# xiao-grove-shield.net
KiCad netlist of a schematic drawn in EAGLE
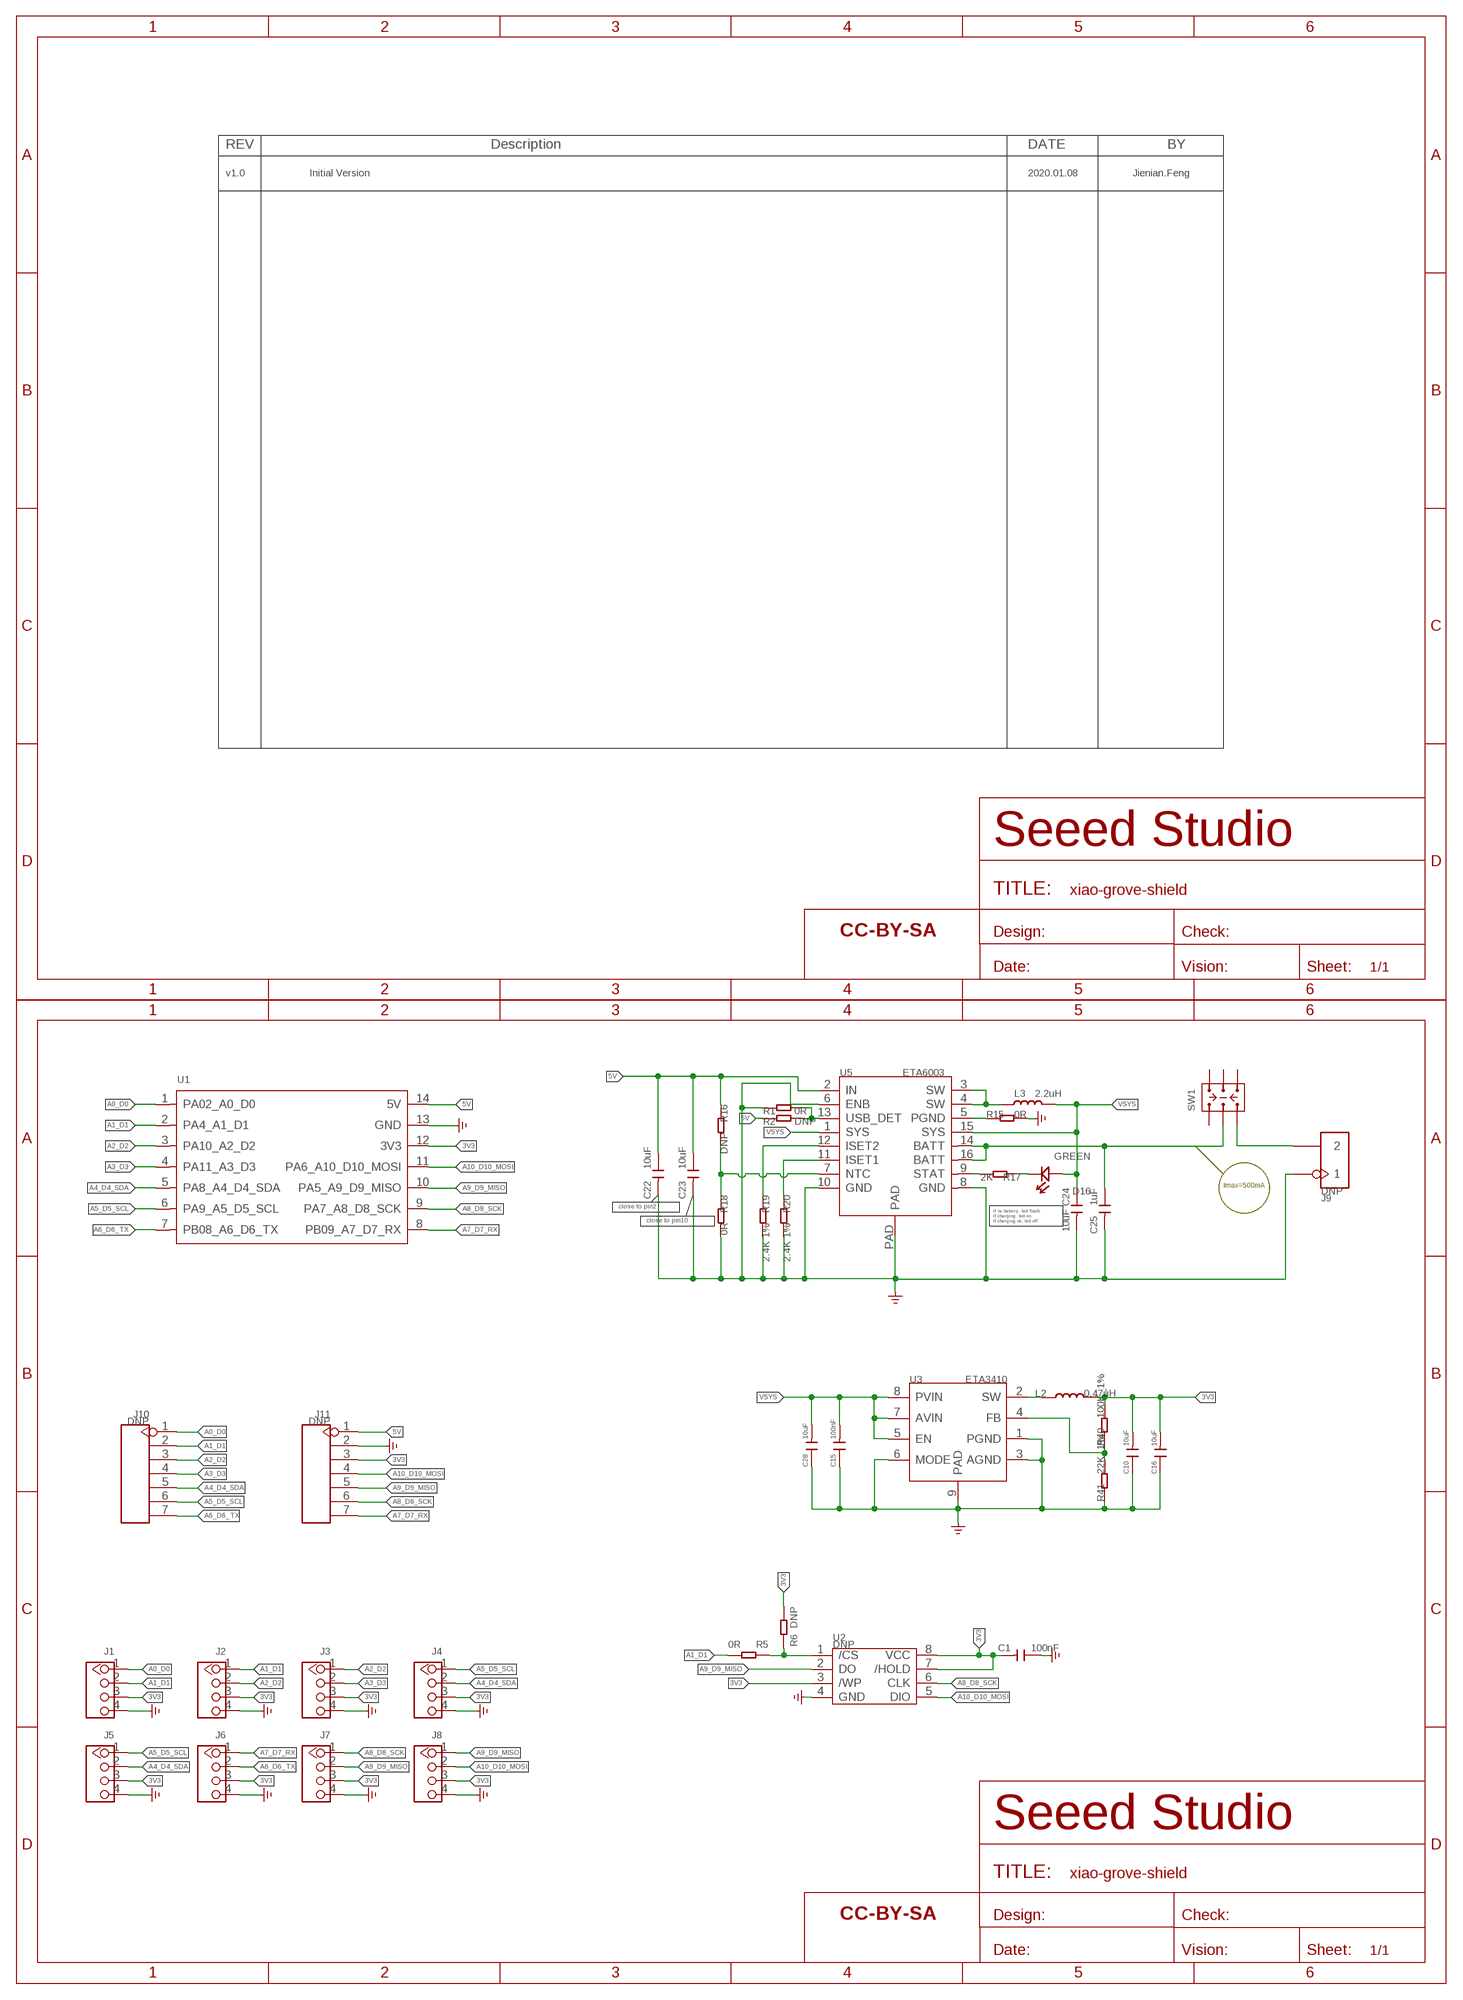
[diagram p0: schematic, sheet 1]

(export (version "E")
  (design (tool "Eeschema 10.0.6"))
  (components
    (comp (ref "C1")
      (value "100nF")
      (footprint "eagle-import:C0402")
      (libsource (lib "eagle-import") (part "CAP-0402"))
    )
    (comp (ref "C10")
      (value "10uF")
      (footprint "eagle-import:C0603")
      (libsource (lib "eagle-import") (part "CAP-0603"))
    )
    (comp (ref "C15")
      (value "100nF")
      (footprint "eagle-import:C0402")
      (libsource (lib "eagle-import") (part "C-0402"))
    )
    (comp (ref "C16")
      (value "10uF")
      (footprint "eagle-import:C0603")
      (libsource (lib "eagle-import") (part "CAP-0603"))
    )
    (comp (ref "C22")
      (value "10uF")
      (footprint "eagle-import:C0603")
      (libsource (lib "eagle-import") (part "CAP-0603"))
    )
    (comp (ref "C23")
      (value "10uF")
      (footprint "eagle-import:C0603")
      (libsource (lib "eagle-import") (part "CAP-0603"))
    )
    (comp (ref "C24")
      (value "10uF")
      (footprint "eagle-import:C0603")
      (libsource (lib "eagle-import") (part "CAP-0603"))
    )
    (comp (ref "C25")
      (value "1uF")
      (footprint "eagle-import:C0402")
      (libsource (lib "eagle-import") (part "C-0402"))
    )
    (comp (ref "C28")
      (value "10uF")
      (footprint "eagle-import:C0603")
      (libsource (lib "eagle-import") (part "CAP-0603"))
    )
    (comp (ref "D16")
      (value "GREEN")
      (footprint "eagle-import:LED-0402")
      (libsource (lib "eagle-import") (part "LED-0402"))
    )
    (comp (ref "FR1")
      (value "SEEEDSTUDIO-OPEN-SCH-FRAME")
      (footprint "eagle-import:SEEEDSTUDIO-PCB-FRAME")
      (libsource (lib "eagle-import") (part "SEEEDSTUDIO-OPEN-SCH-FRAME"))
    )
    (comp (ref "FR2")
      (value "SEEEDSTUDIO-OPEN-SCH-FRAME")
      (footprint "eagle-import:SEEEDSTUDIO-PCB-FRAME")
      (libsource (lib "eagle-import") (part "SEEEDSTUDIO-OPEN-SCH-FRAME"))
    )
    (comp (ref "J1")
      (value "GROVE-CONNECTOR-DIP-320110033")
      (footprint "eagle-import:HW4-2.0")
      (libsource (lib "eagle-import") (part "GROVE-CONNECTOR-DIP-320110033"))
    )
    (comp (ref "J2")
      (value "GROVE-CONNECTOR-DIP-320110033")
      (footprint "eagle-import:HW4-2.0")
      (libsource (lib "eagle-import") (part "GROVE-CONNECTOR-DIP-320110033"))
    )
    (comp (ref "J3")
      (value "GROVE-CONNECTOR-DIP-320110033")
      (footprint "eagle-import:HW4-2.0")
      (libsource (lib "eagle-import") (part "GROVE-CONNECTOR-DIP-320110033"))
    )
    (comp (ref "J4")
      (value "GROVE-CONNECTOR-DIP-320110033")
      (footprint "eagle-import:HW4-2.0")
      (libsource (lib "eagle-import") (part "GROVE-CONNECTOR-DIP-320110033"))
    )
    (comp (ref "J5")
      (value "GROVE-CONNECTOR-DIP-320110033")
      (footprint "eagle-import:HW4-2.0")
      (libsource (lib "eagle-import") (part "GROVE-CONNECTOR-DIP-320110033"))
    )
    (comp (ref "J6")
      (value "GROVE-CONNECTOR-DIP-320110033")
      (footprint "eagle-import:HW4-2.0")
      (libsource (lib "eagle-import") (part "GROVE-CONNECTOR-DIP-320110033"))
    )
    (comp (ref "J7")
      (value "GROVE-CONNECTOR-DIP-320110033")
      (footprint "eagle-import:HW4-2.0")
      (libsource (lib "eagle-import") (part "GROVE-CONNECTOR-DIP-320110033"))
    )
    (comp (ref "J8")
      (value "GROVE-CONNECTOR-DIP-320110033")
      (footprint "eagle-import:HW4-2.0")
      (libsource (lib "eagle-import") (part "GROVE-CONNECTOR-DIP-320110033"))
    )
    (comp (ref "J9")
      (value "DNP")
      (footprint "eagle-import:H2-2.0-C50D30MIL")
      (libsource (lib "eagle-import") (part "HEADER-2P-50/30MIL"))
    )
    (comp (ref "J10")
      (value "DNP")
      (footprint "eagle-import:H7-2.54")
      (libsource (lib "eagle-import") (part "HEADER-7P-2.54"))
    )
    (comp (ref "J11")
      (value "DNP")
      (footprint "eagle-import:H7-2.54")
      (libsource (lib "eagle-import") (part "HEADER-7P-2.54"))
    )
    (comp (ref "L2")
      (value "0.47uH")
      (footprint "eagle-import:L201610")
      (libsource (lib "eagle-import") (part "L-MPM201610SR33_T"))
    )
    (comp (ref "L3")
      (value "2.2uH")
      (footprint "eagle-import:L0805")
      (libsource (lib "eagle-import") (part "INDUCTOR/FERRITE-BEAD'0805'"))
    )
    (comp (ref "R1")
      (value "0R")
      (footprint "eagle-import:R0402")
      (libsource (lib "eagle-import") (part "RES-0402"))
    )
    (comp (ref "R2")
      (value "DNP")
      (footprint "eagle-import:R0402")
      (libsource (lib "eagle-import") (part "RES-0402"))
    )
    (comp (ref "R5")
      (value "0R")
      (footprint "eagle-import:R0402")
      (libsource (lib "eagle-import") (part "RES-0402"))
    )
    (comp (ref "R6")
      (value "DNP")
      (footprint "eagle-import:R0402")
      (libsource (lib "eagle-import") (part "RES-0402"))
    )
    (comp (ref "R15")
      (value "0R")
      (footprint "eagle-import:R0402")
      (libsource (lib "eagle-import") (part "R-0402"))
    )
    (comp (ref "R16")
      (value "DNP")
      (footprint "eagle-import:R0402")
      (libsource (lib "eagle-import") (part "R-0402"))
    )
    (comp (ref "R17")
      (value "2K")
      (footprint "eagle-import:R0402")
      (libsource (lib "eagle-import") (part "R-0402"))
    )
    (comp (ref "R18")
      (value "0R")
      (footprint "eagle-import:R0402")
      (libsource (lib "eagle-import") (part "R-0402"))
    )
    (comp (ref "R19")
      (value "2.4K 1%")
      (footprint "eagle-import:R0402")
      (libsource (lib "eagle-import") (part "R-0402"))
    )
    (comp (ref "R20")
      (value "2.4K 1%")
      (footprint "eagle-import:R0402")
      (libsource (lib "eagle-import") (part "R-0402"))
    )
    (comp (ref "R40")
      (value "100K_1%")
      (footprint "eagle-import:R0402")
      (libsource (lib "eagle-import") (part "R-0402"))
    )
    (comp (ref "R41")
      (value "22K_1%")
      (footprint "eagle-import:R0402")
      (libsource (lib "eagle-import") (part "R-0402"))
    )
    (comp (ref "SW1")
      (value "SWITCH-2CH-6P-311030004")
      (footprint "eagle-import:SW6-2.54-9.0X3.5X3.2MM-90D")
      (libsource (lib "eagle-import") (part "SWITCH-2CH-6P-311030004"))
    )
    (comp (ref "U1")
      (value "MOUDLE-SEEEDUINO-XIAO-DIP")
      (footprint "eagle-import:MOUDLE14P-2.54-21X17.8MM")
      (libsource (lib "eagle-import") (part "MOUDLE-SEEEDUINO-XIAO-DIP"))
    )
    (comp (ref "U2")
      (value "DNP")
      (footprint "eagle-import:SOIC8-1.27-5.3X5.3MM")
      (libsource (lib "eagle-import") (part "FLASH-W25X80-SS"))
    )
    (comp (ref "U3")
      (value "ETA3410")
      (footprint "eagle-import:DFN8G-0.5-2X2MM")
      (libsource (lib "eagle-import") (part "CONVERTER-ETA3410"))
    )
    (comp (ref "U5")
      (value "ETA6003")
      (footprint "eagle-import:QFN16GA-0.5-3X3MM")
      (libsource (lib "eagle-import") (part "PMIC-ETA6003-310990023"))
    )
  )
  (nets
    (net (code "1") (name "3V3") (class "Default")
      (node (ref "C1") (pin "2") (pinfunction "2_2") (pintype "passive"))
      (node (ref "C10") (pin "2") (pinfunction "2_2") (pintype "passive"))
      (node (ref "C16") (pin "2") (pinfunction "2_2") (pintype "passive"))
      (node (ref "J1") (pin "3") (pinfunction "3_3") (pintype "bidirectional"))
      (node (ref "J11") (pin "3") (pinfunction "3_3") (pintype "bidirectional"))
      (node (ref "J2") (pin "3") (pinfunction "3_3") (pintype "bidirectional"))
      (node (ref "J3") (pin "3") (pinfunction "3_3") (pintype "bidirectional"))
      (node (ref "J4") (pin "3") (pinfunction "3_3") (pintype "bidirectional"))
      (node (ref "J5") (pin "3") (pinfunction "3_3") (pintype "bidirectional"))
      (node (ref "J6") (pin "3") (pinfunction "3_3") (pintype "bidirectional"))
      (node (ref "J7") (pin "3") (pinfunction "3_3") (pintype "bidirectional"))
      (node (ref "J8") (pin "3") (pinfunction "3_3") (pintype "bidirectional"))
      (node (ref "L2") (pin "2") (pinfunction "2_2") (pintype "passive"))
      (node (ref "R40") (pin "2") (pinfunction "2_2") (pintype "passive"))
      (node (ref "R6") (pin "1") (pinfunction "1_1") (pintype "passive"))
      (node (ref "U1") (pin "12") (pinfunction "3V3_12") (pintype "bidirectional"))
      (node (ref "U2") (pin "3") (pinfunction "/WP_3") (pintype "bidirectional"))
      (node (ref "U2") (pin "7") (pinfunction "/HOLD_7") (pintype "bidirectional"))
      (node (ref "U2") (pin "8") (pinfunction "VCC_8") (pintype "bidirectional"))
    )
    (net (code "2") (name "5V") (class "Default")
      (node (ref "C22") (pin "1") (pinfunction "1_1") (pintype "passive"))
      (node (ref "C23") (pin "1") (pinfunction "1_1") (pintype "passive"))
      (node (ref "J11") (pin "1") (pinfunction "1_1") (pintype "bidirectional"))
      (node (ref "R16") (pin "1") (pinfunction "1_1") (pintype "passive"))
      (node (ref "R2") (pin "1") (pinfunction "1_1") (pintype "passive"))
      (node (ref "U1") (pin "14") (pinfunction "5V_14") (pintype "bidirectional"))
      (node (ref "U5") (pin "2") (pinfunction "IN_2") (pintype "bidirectional"))
    )
    (net (code "3") (name "A0_D0") (class "Default")
      (node (ref "J1") (pin "1") (pinfunction "1_1") (pintype "bidirectional"))
      (node (ref "J10") (pin "1") (pinfunction "1_1") (pintype "bidirectional"))
      (node (ref "U1") (pin "1") (pinfunction "PA02_A0_D0_1") (pintype "bidirectional"))
    )
    (net (code "4") (name "A1_D1") (class "Default")
      (node (ref "J1") (pin "2") (pinfunction "2_2") (pintype "bidirectional"))
      (node (ref "J10") (pin "2") (pinfunction "2_2") (pintype "bidirectional"))
      (node (ref "J2") (pin "1") (pinfunction "1_1") (pintype "bidirectional"))
      (node (ref "R5") (pin "1") (pinfunction "1_1") (pintype "passive"))
      (node (ref "U1") (pin "2") (pinfunction "PA4_A1_D1_2") (pintype "bidirectional"))
    )
    (net (code "5") (name "A2_D2") (class "Default")
      (node (ref "J10") (pin "3") (pinfunction "3_3") (pintype "bidirectional"))
      (node (ref "J2") (pin "2") (pinfunction "2_2") (pintype "bidirectional"))
      (node (ref "J3") (pin "1") (pinfunction "1_1") (pintype "bidirectional"))
      (node (ref "U1") (pin "3") (pinfunction "PA10_A2_D2_3") (pintype "bidirectional"))
    )
    (net (code "6") (name "A3_D3") (class "Default")
      (node (ref "J10") (pin "4") (pinfunction "4_4") (pintype "bidirectional"))
      (node (ref "J3") (pin "2") (pinfunction "2_2") (pintype "bidirectional"))
      (node (ref "U1") (pin "4") (pinfunction "PA11_A3_D3_4") (pintype "bidirectional"))
    )
    (net (code "7") (name "A4_D4_SDA") (class "Default")
      (node (ref "J10") (pin "5") (pinfunction "5_5") (pintype "bidirectional"))
      (node (ref "J4") (pin "2") (pinfunction "2_2") (pintype "bidirectional"))
      (node (ref "J5") (pin "2") (pinfunction "2_2") (pintype "bidirectional"))
      (node (ref "U1") (pin "5") (pinfunction "PA8_A4_D4_SDA_5") (pintype "bidirectional"))
    )
    (net (code "8") (name "A5_D5_SCL") (class "Default")
      (node (ref "J10") (pin "6") (pinfunction "6_6") (pintype "bidirectional"))
      (node (ref "J4") (pin "1") (pinfunction "1_1") (pintype "bidirectional"))
      (node (ref "J5") (pin "1") (pinfunction "1_1") (pintype "bidirectional"))
      (node (ref "U1") (pin "6") (pinfunction "PA9_A5_D5_SCL_6") (pintype "bidirectional"))
    )
    (net (code "9") (name "A6_D6_TX") (class "Default")
      (node (ref "J10") (pin "7") (pinfunction "7_7") (pintype "bidirectional"))
      (node (ref "J6") (pin "2") (pinfunction "2_2") (pintype "bidirectional"))
      (node (ref "U1") (pin "7") (pinfunction "PB08_A6_D6_TX_7") (pintype "bidirectional"))
    )
    (net (code "10") (name "A7_D7_RX") (class "Default")
      (node (ref "J11") (pin "7") (pinfunction "7_7") (pintype "bidirectional"))
      (node (ref "J6") (pin "1") (pinfunction "1_1") (pintype "bidirectional"))
      (node (ref "U1") (pin "8") (pinfunction "PB09_A7_D7_RX_8") (pintype "bidirectional"))
    )
    (net (code "11") (name "A8_D8_SCK") (class "Default")
      (node (ref "J11") (pin "6") (pinfunction "6_6") (pintype "bidirectional"))
      (node (ref "J7") (pin "1") (pinfunction "1_1") (pintype "bidirectional"))
      (node (ref "U1") (pin "9") (pinfunction "PA7_A8_D8_SCK_9") (pintype "bidirectional"))
      (node (ref "U2") (pin "6") (pinfunction "CLK_6") (pintype "bidirectional"))
    )
    (net (code "12") (name "A9_D9_MISO") (class "Default")
      (node (ref "J11") (pin "5") (pinfunction "5_5") (pintype "bidirectional"))
      (node (ref "J7") (pin "2") (pinfunction "2_2") (pintype "bidirectional"))
      (node (ref "J8") (pin "1") (pinfunction "1_1") (pintype "bidirectional"))
      (node (ref "U1") (pin "10") (pinfunction "PA5_A9_D9_MISO_10") (pintype "bidirectional"))
      (node (ref "U2") (pin "2") (pinfunction "DO_2") (pintype "bidirectional"))
    )
    (net (code "13") (name "A10_D10_MOSI") (class "Default")
      (node (ref "J11") (pin "4") (pinfunction "4_4") (pintype "bidirectional"))
      (node (ref "J8") (pin "2") (pinfunction "2_2") (pintype "bidirectional"))
      (node (ref "U1") (pin "11") (pinfunction "PA6_A10_D10_MOSI_11") (pintype "bidirectional"))
      (node (ref "U2") (pin "5") (pinfunction "DIO_5") (pintype "bidirectional"))
    )
    (net (code "14") (name "GND_POWER") (class "Default")
      (node (ref "C1") (pin "1") (pinfunction "1_1") (pintype "passive"))
      (node (ref "C10") (pin "1") (pinfunction "1_1") (pintype "passive"))
      (node (ref "C15") (pin "1") (pinfunction "1_1") (pintype "passive"))
      (node (ref "C16") (pin "1") (pinfunction "1_1") (pintype "passive"))
      (node (ref "C22") (pin "2") (pinfunction "2_2") (pintype "passive"))
      (node (ref "C23") (pin "2") (pinfunction "2_2") (pintype "passive"))
      (node (ref "C24") (pin "2") (pinfunction "2_2") (pintype "passive"))
      (node (ref "C25") (pin "2") (pinfunction "2_2") (pintype "passive"))
      (node (ref "C28") (pin "1") (pinfunction "1_1") (pintype "passive"))
      (node (ref "J1") (pin "4") (pinfunction "4_4") (pintype "bidirectional"))
      (node (ref "J11") (pin "2") (pinfunction "2_2") (pintype "bidirectional"))
      (node (ref "J2") (pin "4") (pinfunction "4_4") (pintype "bidirectional"))
      (node (ref "J3") (pin "4") (pinfunction "4_4") (pintype "bidirectional"))
      (node (ref "J4") (pin "4") (pinfunction "4_4") (pintype "bidirectional"))
      (node (ref "J5") (pin "4") (pinfunction "4_4") (pintype "bidirectional"))
      (node (ref "J6") (pin "4") (pinfunction "4_4") (pintype "bidirectional"))
      (node (ref "J7") (pin "4") (pinfunction "4_4") (pintype "bidirectional"))
      (node (ref "J8") (pin "4") (pinfunction "4_4") (pintype "bidirectional"))
      (node (ref "J9") (pin "1") (pinfunction "1_1") (pintype "bidirectional"))
      (node (ref "R1") (pin "1") (pinfunction "1_1") (pintype "passive"))
      (node (ref "R15") (pin "2") (pinfunction "2_2") (pintype "passive"))
      (node (ref "R18") (pin "2") (pinfunction "2_2") (pintype "passive"))
      (node (ref "R19") (pin "2") (pinfunction "2_2") (pintype "passive"))
      (node (ref "R20") (pin "2") (pinfunction "2_2") (pintype "passive"))
      (node (ref "R41") (pin "1") (pinfunction "1_1") (pintype "passive"))
      (node (ref "U1") (pin "13") (pinfunction "GND_13") (pintype "bidirectional"))
      (node (ref "U2") (pin "4") (pinfunction "GND_4") (pintype "bidirectional"))
      (node (ref "U3") (pin "1") (pinfunction "PGND_1") (pintype "bidirectional"))
      (node (ref "U3") (pin "3") (pinfunction "AGND_3") (pintype "bidirectional"))
      (node (ref "U3") (pin "6") (pinfunction "MODE_6") (pintype "bidirectional"))
      (node (ref "U3") (pin "9") (pinfunction "PAD_9") (pintype "bidirectional"))
      (node (ref "U5") (pin "10") (pinfunction "GND_10") (pintype "bidirectional"))
      (node (ref "U5") (pin "6") (pinfunction "ENB_6") (pintype "bidirectional"))
      (node (ref "U5") (pin "8") (pinfunction "GND_8") (pintype "bidirectional"))
      (node (ref "U5") (pin "PAD") (pinfunction "PAD_PAD") (pintype "bidirectional"))
    )
    (net (code "15") (name "Net-(C25-Pad1)") (class "Default")
      (node (ref "C25") (pin "1") (pinfunction "1_1") (pintype "passive"))
      (node (ref "SW1") (pin "COM1") (pinfunction "COM1_COM1") (pintype "bidirectional"))
      (node (ref "U5") (pin "14") (pinfunction "BATT_14") (pintype "bidirectional"))
      (node (ref "U5") (pin "16") (pinfunction "BATT_16") (pintype "bidirectional"))
    )
    (net (code "16") (name "Net-(D16-Pad-)") (class "Default")
      (node (ref "D16") (pin "-") (pinfunction "-_-") (pintype "passive"))
      (node (ref "R17") (pin "1") (pinfunction "1_1") (pintype "passive"))
    )
    (net (code "17") (name "Net-(J9-Pad2)") (class "Default")
      (node (ref "J9") (pin "2") (pinfunction "2_2") (pintype "bidirectional"))
      (node (ref "SW1") (pin "CH1B") (pinfunction "CH1B_CH1B") (pintype "bidirectional"))
    )
    (net (code "18") (name "Net-(L3-Pad1)") (class "Default")
      (node (ref "L3") (pin "1") (pinfunction "1_1") (pintype "passive"))
      (node (ref "U5") (pin "3") (pinfunction "SW_3") (pintype "bidirectional"))
      (node (ref "U5") (pin "4") (pinfunction "SW_4") (pintype "bidirectional"))
    )
    (net (code "19") (name "Net-(U2-{slash}CS)") (class "Default")
      (node (ref "R5") (pin "2") (pinfunction "2_2") (pintype "passive"))
      (node (ref "R6") (pin "2") (pinfunction "2_2") (pintype "passive"))
      (node (ref "U2") (pin "1") (pinfunction "/CS_1") (pintype "bidirectional"))
    )
    (net (code "20") (name "Net-(U3-FB)") (class "Default")
      (node (ref "R40") (pin "1") (pinfunction "1_1") (pintype "passive"))
      (node (ref "R41") (pin "2") (pinfunction "2_2") (pintype "passive"))
      (node (ref "U3") (pin "4") (pinfunction "FB_4") (pintype "bidirectional"))
    )
    (net (code "21") (name "Net-(U3-SW)") (class "Default")
      (node (ref "L2") (pin "1") (pinfunction "1_1") (pintype "passive"))
      (node (ref "U3") (pin "2") (pinfunction "SW_2") (pintype "bidirectional"))
    )
    (net (code "22") (name "Net-(U5-ISET1)") (class "Default")
      (node (ref "R20") (pin "1") (pinfunction "1_1") (pintype "passive"))
      (node (ref "U5") (pin "11") (pinfunction "ISET1_11") (pintype "bidirectional"))
    )
    (net (code "23") (name "Net-(U5-ISET2)") (class "Default")
      (node (ref "R19") (pin "1") (pinfunction "1_1") (pintype "passive"))
      (node (ref "U5") (pin "12") (pinfunction "ISET2_12") (pintype "bidirectional"))
    )
    (net (code "24") (name "Net-(U5-NTC)") (class "Default")
      (node (ref "R16") (pin "2") (pinfunction "2_2") (pintype "passive"))
      (node (ref "R18") (pin "1") (pinfunction "1_1") (pintype "passive"))
      (node (ref "U5") (pin "7") (pinfunction "NTC_7") (pintype "bidirectional"))
    )
    (net (code "25") (name "Net-(U5-PGND)") (class "Default")
      (node (ref "R15") (pin "1") (pinfunction "1_1") (pintype "passive"))
      (node (ref "U5") (pin "5") (pinfunction "PGND_5") (pintype "bidirectional"))
    )
    (net (code "26") (name "Net-(U5-STAT)") (class "Default")
      (node (ref "R17") (pin "2") (pinfunction "2_2") (pintype "passive"))
      (node (ref "U5") (pin "9") (pinfunction "STAT_9") (pintype "bidirectional"))
    )
    (net (code "27") (name "Net-(U5-USB_DET)") (class "Default")
      (node (ref "R1") (pin "2") (pinfunction "2_2") (pintype "passive"))
      (node (ref "R2") (pin "2") (pinfunction "2_2") (pintype "passive"))
      (node (ref "U5") (pin "13") (pinfunction "USB_DET_13") (pintype "bidirectional"))
    )
    (net (code "28") (name "VSYS") (class "Default")
      (node (ref "C15") (pin "2") (pinfunction "2_2") (pintype "passive"))
      (node (ref "C24") (pin "1") (pinfunction "1_1") (pintype "passive"))
      (node (ref "C28") (pin "2") (pinfunction "2_2") (pintype "passive"))
      (node (ref "D16") (pin "+") (pinfunction "+_+") (pintype "passive"))
      (node (ref "L3") (pin "2") (pinfunction "2_2") (pintype "passive"))
      (node (ref "U3") (pin "5") (pinfunction "EN_5") (pintype "bidirectional"))
      (node (ref "U3") (pin "7") (pinfunction "AVIN_7") (pintype "bidirectional"))
      (node (ref "U3") (pin "8") (pinfunction "PVIN_8") (pintype "bidirectional"))
      (node (ref "U5") (pin "1") (pinfunction "SYS_1") (pintype "bidirectional"))
      (node (ref "U5") (pin "15") (pinfunction "SYS_15") (pintype "bidirectional"))
    )
    (net (code "29") (name "unconnected-(SW1-PadCH1A)") (class "Default")
      (node (ref "SW1") (pin "CH1A") (pinfunction "CH1A_CH1A") (pintype "bidirectional"))
    )
    (net (code "30") (name "unconnected-(SW1-PadCH2A)") (class "Default")
      (node (ref "SW1") (pin "CH2A") (pinfunction "CH2A_CH2A") (pintype "bidirectional"))
    )
    (net (code "31") (name "unconnected-(SW1-PadCH2B)") (class "Default")
      (node (ref "SW1") (pin "CH2B") (pinfunction "CH2B_CH2B") (pintype "bidirectional"))
    )
    (net (code "32") (name "unconnected-(SW1-PadCOM2)") (class "Default")
      (node (ref "SW1") (pin "COM2") (pinfunction "COM2_COM2") (pintype "bidirectional"))
    )
  )
)
